# regulator9V.net
KiCad netlist of a schematic drawn in Altium Designer
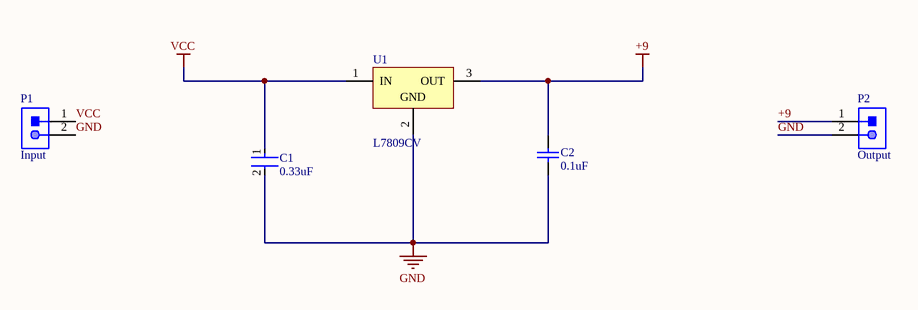
[diagram p0: regulator9V.SchDoc]

(export (version "E")
  (design (tool "Eeschema 10.0.6"))
  (components
    (comp (ref "C1")
      (value "0.33uF")
      (footprint "FP-RDE1K1-MFG")
      (description "Ceramic Capacitor 330nF ±10% 50V X7R Radial")
      (fields (field (name "TOLERANCE") "10%"))
      (libsource (lib "Altium Content Vault") (part "02cd4be3c70576c341d710602a673aa"))
    )
    (comp (ref "C2")
      (value "0.1uF")
      (footprint "AVX-SA115C104KAR")
      (fields (field (name "TOLERANCE") "±10%") (field (name "MANUFACTURER") "AVX"))
      (libsource (lib "Altium Content Vault") (part "CAP-NP-2"))
    )
    (comp (ref "P1")
      (value "Input")
      (footprint "JST-S2B-PH-K-S_V")
      (fields (field (name "TOLERANCE") "20%"))
      (libsource (lib "Altium Content Vault") (part "CN-1P-M-R2"))
    )
    (comp (ref "P2")
      (value "Output")
      (footprint "JST-S2B-PH-K-S_V")
      (fields (field (name "TOLERANCE") "20%"))
      (libsource (lib "") (part "CN-1P-M-R2_1"))
    )
    (comp (ref "U1")
      (value "L7809CV")
      (footprint "TO220")
      (description "Positive Voltage Regulator, 9V, 3-Pin TO-220")
      (libsource (lib "Altium Content Vault") (part "PM-REG-L4940-SIL3"))
    )
  )
  (nets
    (net (code "1") (name "+9") (class "Default")
      (node (ref "C2") (pin "2") (pinfunction "2_2") (pintype "passive"))
      (node (ref "P2") (pin "1") (pinfunction "1_1") (pintype "passive"))
      (node (ref "U1") (pin "3") (pinfunction "OUT_3") (pintype "power_in"))
    )
    (net (code "2") (name "GND") (class "Default")
      (node (ref "C1") (pin "2") (pinfunction "2_2") (pintype "passive"))
      (node (ref "C2") (pin "1") (pinfunction "1_1") (pintype "passive"))
      (node (ref "P1") (pin "2") (pinfunction "2_2") (pintype "passive"))
      (node (ref "P2") (pin "2") (pinfunction "2_2") (pintype "passive"))
      (node (ref "U1") (pin "2") (pinfunction "GND_2") (pintype "power_in"))
    )
    (net (code "3") (name "VCC") (class "Default")
      (node (ref "C1") (pin "1") (pinfunction "1_1") (pintype "passive"))
      (node (ref "P1") (pin "1") (pinfunction "1_1") (pintype "passive"))
      (node (ref "U1") (pin "1") (pinfunction "IN_1") (pintype "power_in"))
    )
  )
)
